# HeadController.net
KiCad netlist of a schematic drawn in Altium Designer
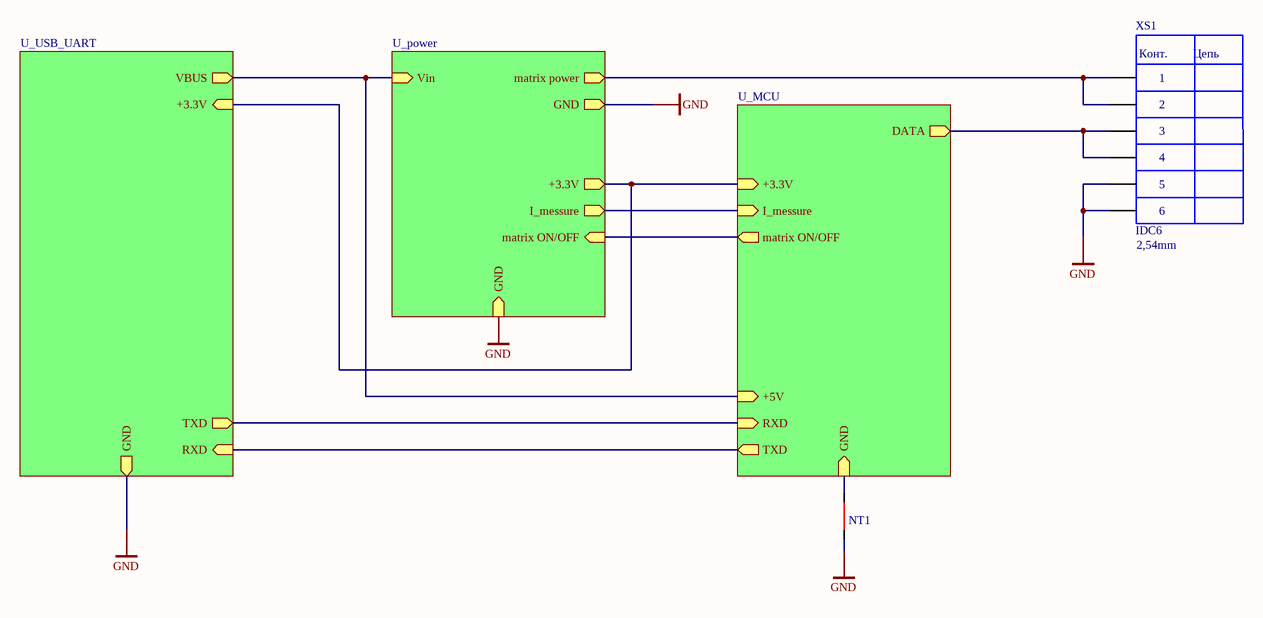
[diagram p0: HeadController.SchDoc]

(export (version "E")
  (design (tool "Eeschema 10.0.6"))
  (components
    (comp (ref "NT1") (value "~") (footprint "NT") (libsource (lib "MechanikLibrary") (part "NT")))
    (comp (ref "XS1")
      (value "IDC6")
      (footprint "IDC-6 (2.54) (end face)")
      (fields (field (name "PACKAGE") "2,54mm"))
      (libsource (lib "MechanikLibrary") (part "IDC6"))
    )
  )
  (nets
    (net (code "2") (name "/DATA") (class "Default")
      (node (ref "XS1") (pin "3") (pintype "passive"))
      (node (ref "XS1") (pin "4") (pintype "passive"))
    )
    (net (code "3") (name "/GND") (class "Default") (node (ref "NT1") (pin "1") (pintype "passive")))
    (net (code "9") (name "/matrix power") (class "Default")
      (node (ref "XS1") (pin "1") (pintype "passive"))
      (node (ref "XS1") (pin "2") (pintype "passive"))
    )
    (net (code "10") (name "GND") (class "Default")
      (node (ref "NT1") (pin "2") (pintype "passive"))
      (node (ref "XS1") (pin "5") (pintype "passive"))
      (node (ref "XS1") (pin "6") (pintype "passive"))
    )
  )
)
